# MCU.net
KiCad netlist of a schematic drawn in Altium Designer
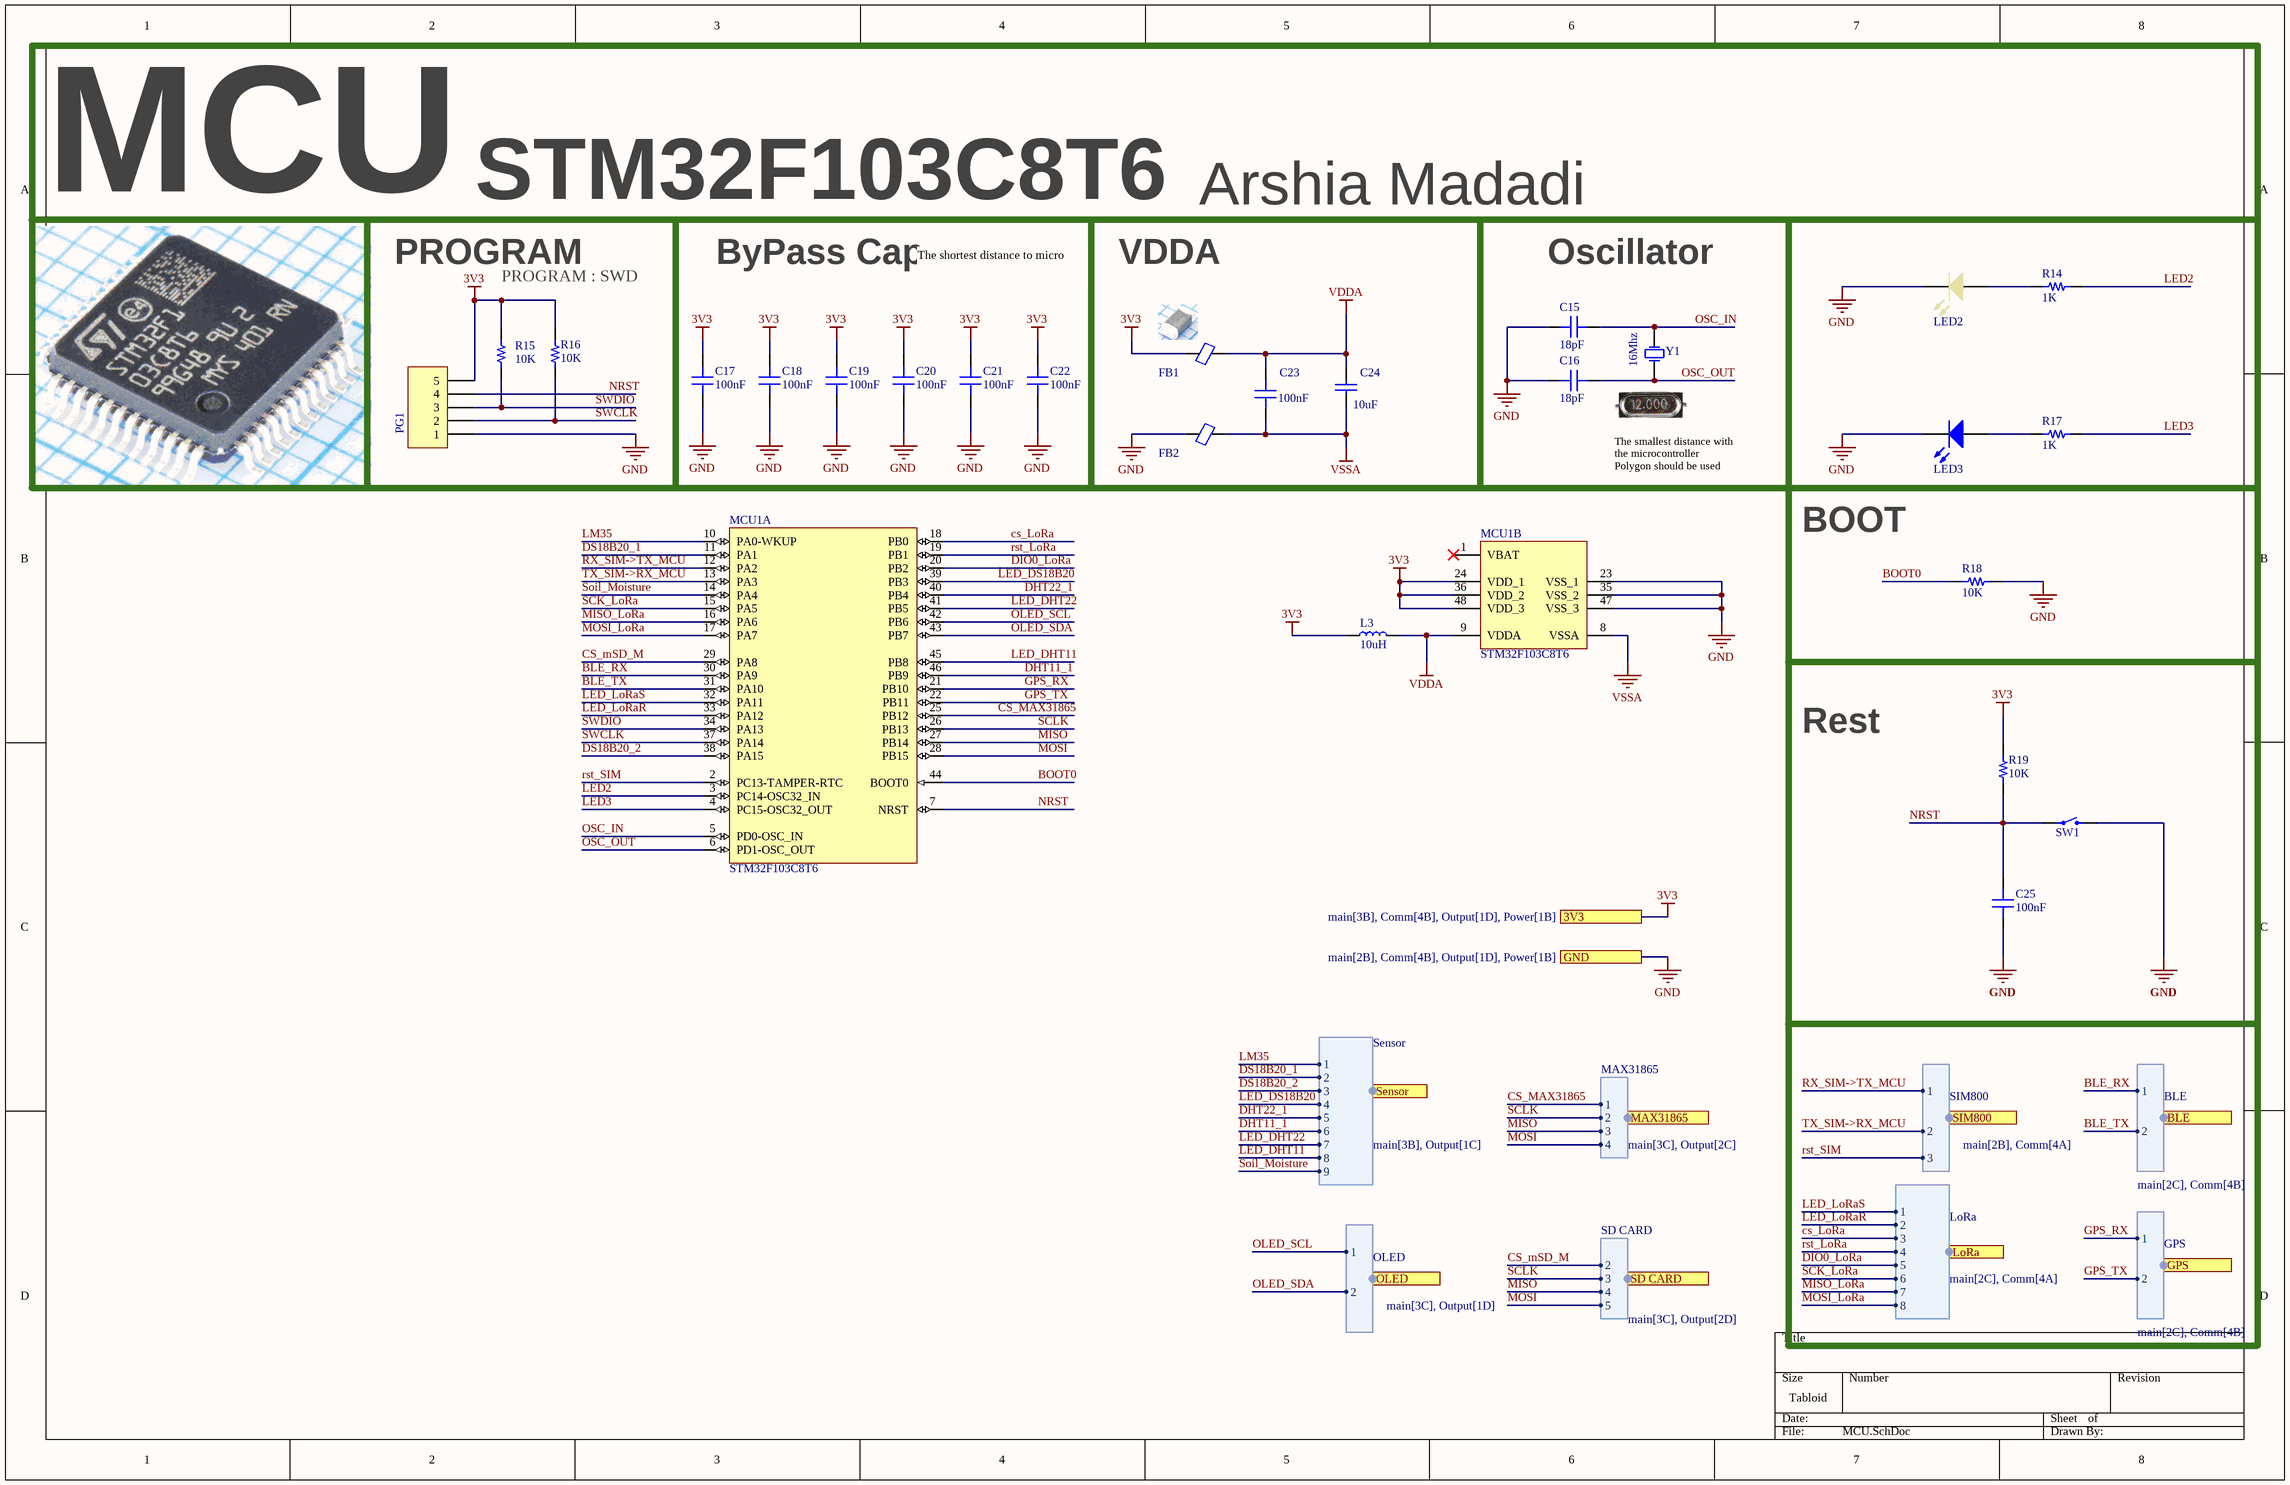
[diagram p0: MCU.SchDoc]

(export (version "E")
  (design (tool "Eeschema 10.0.6"))
  (components
    (comp (ref "C15")
      (value "18pF")
      (footprint "CAP 0603_1608")
      (description "SMT Capacitor")
      (libsource (lib "Capacitor") (part "Cap 0603"))
    )
    (comp (ref "C16")
      (value "18pF")
      (footprint "CAP 0603_1608")
      (description "SMT Capacitor")
      (libsource (lib "Capacitor") (part "Cap 0603"))
    )
    (comp (ref "C17")
      (value "100nF")
      (footprint "CAP 0603_1608")
      (description "SMT Capacitor")
      (libsource (lib "Capacitor") (part "Cap 0603"))
    )
    (comp (ref "C18")
      (value "100nF")
      (footprint "CAP 0603_1608")
      (description "SMT Capacitor")
      (libsource (lib "Capacitor") (part "Cap 0603"))
    )
    (comp (ref "C19")
      (value "100nF")
      (footprint "CAP 0603_1608")
      (description "SMT Capacitor")
      (libsource (lib "Capacitor") (part "Cap 0603"))
    )
    (comp (ref "C20")
      (value "100nF")
      (footprint "CAP 0603_1608")
      (description "SMT Capacitor")
      (libsource (lib "Capacitor") (part "Cap 0603"))
    )
    (comp (ref "C21")
      (value "100nF")
      (footprint "CAP 0603_1608")
      (description "SMT Capacitor")
      (libsource (lib "Capacitor") (part "Cap 0603"))
    )
    (comp (ref "C22")
      (value "100nF")
      (footprint "CAP 0603_1608")
      (description "SMT Capacitor")
      (libsource (lib "Capacitor") (part "Cap 0603"))
    )
    (comp (ref "C23")
      (value "100nF")
      (footprint "CAP 0603_1608")
      (description "SMT Capacitor")
      (libsource (lib "Capacitor") (part "Cap 0603"))
    )
    (comp (ref "C24")
      (value "10uF")
      (footprint "MY_CAP_SMD_0603")
      (description "1.6 mm × 0.8 mm")
      (libsource (lib "AMINLIB") (part "CAP SMD_0603"))
    )
    (comp (ref "C25")
      (value "100nF")
      (footprint "CAP 0603_1608")
      (description "SMT Capacitor")
      (libsource (lib "Capacitor") (part "Cap 0603"))
    )
    (comp (ref "FB1")
      (value "Ferrite Bead SMD")
      (footprint "FB1206")
      (fields (field (name "DESIGNER") "Ali Hafizi"))
      (libsource (lib "Altium") (part "Ferrite Bead SMD Package"))
    )
    (comp (ref "FB2")
      (value "Ferrite Bead SMD")
      (footprint "FB1206")
      (fields (field (name "DESIGNER") "Ali Hafizi"))
      (libsource (lib "Altium") (part "Ferrite Bead SMD Package"))
    )
    (comp (ref "L3")
      (value "10uH")
      (footprint "IND 1206_3216")
      (description "SMT Inductor")
      (libsource (lib "Inductor") (part "Ind 1206"))
    )
    (comp (ref "LED2")
      (value "LED SMD 0805 WHITE")
      (footprint "LED_0805_WHITE")
      (libsource (lib "Led") (part "LED SMD 0805 WHITE"))
    )
    (comp (ref "LED3")
      (value "LED SMD 0805 BLUE")
      (footprint "LED_0805_RED")
      (libsource (lib "Led") (part "LED SMD 0805 BLUE"))
    )
    (comp (ref "MCU1")
      (value "STM32F103C8T6")
      (footprint "QFP50P900X900X160-48N")
      (libsource (lib "STMicroelectronics STM32 F1") (part "STM32F103C8T6"))
    )
    (comp (ref "PG1")
      (value "Header 5")
      (footprint "My_1X05")
      (description "Header, 5-Pin")
      (fields (field (name "PUBLISHER") "Altium Limited"))
      (libsource (lib "AMINLIB") (part "Header 5"))
    )
    (comp (ref "R14")
      (value "1K")
      (footprint "RES 0603_1608")
      (description "SMT Resistor")
      (libsource (lib "Resistor") (part "Res 0603"))
    )
    (comp (ref "R15")
      (value "10K")
      (footprint "RES 0603_1608")
      (description "SMT Resistor")
      (libsource (lib "Resistor") (part "Res 0603"))
    )
    (comp (ref "R16")
      (value "10K")
      (footprint "RES 0603_1608")
      (description "SMT Resistor")
      (libsource (lib "Resistor") (part "Res 0603"))
    )
    (comp (ref "R17")
      (value "1K")
      (footprint "RES 0603_1608")
      (description "SMT Resistor")
      (libsource (lib "Resistor") (part "Res 0603"))
    )
    (comp (ref "R18")
      (value "10K")
      (footprint "RES 0603_1608")
      (description "SMT Resistor")
      (libsource (lib "Resistor") (part "Res 0603"))
    )
    (comp (ref "R19")
      (value "10K")
      (footprint "RES 0603_1608")
      (description "SMT Resistor")
      (libsource (lib "Resistor") (part "Res 0603"))
    )
    (comp (ref "SW1")
      (value "Tactile 2PIN 6X3.5mm H4.57mm (SMD)")
      (footprint "SWPBS_SPST_6X3X5")
      (description "Tactile Switch SPST-NO Top Actuated Surface Mount")
      (fields (field (name "PARTNUMBER") "FSMSMTR-ND"))
      (libsource (lib "Switch") (part "Tactile 2PIN 6X3.5mm H4.57mm (SMD)"))
    )
    (comp (ref "Y1")
      (value "16Mhz")
      (footprint "Crystal")
      (description "Crystal Oscillator")
      (fields (field (name "PUBLISHER") "Altium Limited"))
      (libsource (lib "Sajad_Altium_Library") (part "XTAL"))
    )
  )
  (nets
    (net (code "10") (name "/BLE_RX") (class "Default")
      (node (ref "MCU1") (pin "30") (pinfunction "PA9_30") (pintype "bidirectional"))
    )
    (net (code "11") (name "/BLE_TX") (class "Default")
      (node (ref "MCU1") (pin "31") (pinfunction "PA10_31") (pintype "bidirectional"))
    )
    (net (code "12") (name "/BOOT0") (class "Default")
      (node (ref "MCU1") (pin "44") (pinfunction "BOOT0_44") (pintype "input"))
      (node (ref "R18") (pin "2") (pinfunction "2_2") (pintype "passive"))
    )
    (net (code "13") (name "/CS_MAX31865") (class "Default")
      (node (ref "MCU1") (pin "25") (pinfunction "PB12_25") (pintype "bidirectional"))
    )
    (net (code "14") (name "/CS_mSD_M") (class "Default")
      (node (ref "MCU1") (pin "29") (pinfunction "PA8_29") (pintype "bidirectional"))
    )
    (net (code "15") (name "/DHT11_1") (class "Default")
      (node (ref "MCU1") (pin "46") (pinfunction "PB9_46") (pintype "bidirectional"))
    )
    (net (code "16") (name "/DHT22_1") (class "Default")
      (node (ref "MCU1") (pin "40") (pinfunction "PB4_40") (pintype "bidirectional"))
    )
    (net (code "17") (name "/DIO0_LoRa") (class "Default")
      (node (ref "MCU1") (pin "20") (pinfunction "PB2_20") (pintype "bidirectional"))
    )
    (net (code "18") (name "/DS18B20_1") (class "Default")
      (node (ref "MCU1") (pin "11") (pinfunction "PA1_11") (pintype "bidirectional"))
    )
    (net (code "19") (name "/DS18B20_2") (class "Default")
      (node (ref "MCU1") (pin "38") (pinfunction "PA15_38") (pintype "bidirectional"))
    )
    (net (code "20") (name "/GPS_RX") (class "Default")
      (node (ref "MCU1") (pin "21") (pinfunction "PB10_21") (pintype "bidirectional"))
    )
    (net (code "21") (name "/GPS_TX") (class "Default")
      (node (ref "MCU1") (pin "22") (pinfunction "PB11_22") (pintype "bidirectional"))
    )
    (net (code "22") (name "/LED2") (class "Default")
      (node (ref "MCU1") (pin "3") (pinfunction "PC14-OSC32_IN_3") (pintype "bidirectional"))
      (node (ref "R14") (pin "1") (pinfunction "1_1") (pintype "passive"))
    )
    (net (code "23") (name "/LED3") (class "Default")
      (node (ref "MCU1") (pin "4") (pinfunction "PC15-OSC32_OUT_4") (pintype "bidirectional"))
      (node (ref "R17") (pin "1") (pinfunction "1_1") (pintype "passive"))
    )
    (net (code "24") (name "/LED_DHT11") (class "Default")
      (node (ref "MCU1") (pin "45") (pinfunction "PB8_45") (pintype "bidirectional"))
    )
    (net (code "25") (name "/LED_DHT22") (class "Default")
      (node (ref "MCU1") (pin "41") (pinfunction "PB5_41") (pintype "bidirectional"))
    )
    (net (code "26") (name "/LED_DS18B20") (class "Default")
      (node (ref "MCU1") (pin "39") (pinfunction "PB3_39") (pintype "bidirectional"))
    )
    (net (code "27") (name "/LED_LoRaR") (class "Default")
      (node (ref "MCU1") (pin "33") (pinfunction "PA12_33") (pintype "bidirectional"))
    )
    (net (code "28") (name "/LED_LoRaS") (class "Default")
      (node (ref "MCU1") (pin "32") (pinfunction "PA11_32") (pintype "bidirectional"))
    )
    (net (code "29") (name "/LM35") (class "Default")
      (node (ref "MCU1") (pin "10") (pinfunction "PA0-WKUP_10") (pintype "bidirectional"))
    )
    (net (code "30") (name "/MISO") (class "Default")
      (node (ref "MCU1") (pin "27") (pinfunction "PB14_27") (pintype "bidirectional"))
    )
    (net (code "31") (name "/MISO_LoRa") (class "Default")
      (node (ref "MCU1") (pin "16") (pinfunction "PA6_16") (pintype "bidirectional"))
    )
    (net (code "32") (name "/MOSI") (class "Default")
      (node (ref "MCU1") (pin "28") (pinfunction "PB15_28") (pintype "bidirectional"))
    )
    (net (code "33") (name "/MOSI_LoRa") (class "Default")
      (node (ref "MCU1") (pin "17") (pinfunction "PA7_17") (pintype "bidirectional"))
    )
    (net (code "34") (name "/NRST") (class "Default")
      (node (ref "C25") (pin "2") (pinfunction "2_2") (pintype "passive"))
      (node (ref "MCU1") (pin "7") (pinfunction "NRST_7") (pintype "bidirectional"))
      (node (ref "PG1") (pin "4") (pinfunction "4_4") (pintype "passive"))
      (node (ref "R19") (pin "2") (pinfunction "2_2") (pintype "passive"))
      (node (ref "SW1") (pin "1") (pinfunction "1_1") (pintype "passive"))
    )
    (net (code "35") (name "/OLED_SCL") (class "Default")
      (node (ref "MCU1") (pin "42") (pinfunction "PB6_42") (pintype "bidirectional"))
    )
    (net (code "36") (name "/OLED_SDA") (class "Default")
      (node (ref "MCU1") (pin "43") (pinfunction "PB7_43") (pintype "bidirectional"))
    )
    (net (code "37") (name "/OSC_IN") (class "Default")
      (node (ref "C15") (pin "1") (pinfunction "1_1") (pintype "passive"))
      (node (ref "MCU1") (pin "5") (pinfunction "PD0-OSC_IN_5") (pintype "bidirectional"))
      (node (ref "Y1") (pin "2") (pinfunction "OSC2_2") (pintype "passive"))
    )
    (net (code "38") (name "/OSC_OUT") (class "Default")
      (node (ref "C16") (pin "1") (pinfunction "1_1") (pintype "passive"))
      (node (ref "MCU1") (pin "6") (pinfunction "PD1-OSC_OUT_6") (pintype "bidirectional"))
      (node (ref "Y1") (pin "1") (pinfunction "OSC1_1") (pintype "passive"))
    )
    (net (code "39") (name "/RX_SIM->TX_MCU") (class "Default")
      (node (ref "MCU1") (pin "12") (pinfunction "PA2_12") (pintype "bidirectional"))
    )
    (net (code "40") (name "/SCK_LoRa") (class "Default")
      (node (ref "MCU1") (pin "15") (pinfunction "PA5_15") (pintype "bidirectional"))
    )
    (net (code "41") (name "/SCLK") (class "Default")
      (node (ref "MCU1") (pin "26") (pinfunction "PB13_26") (pintype "bidirectional"))
    )
    (net (code "42") (name "/SWCLK") (class "Default")
      (node (ref "MCU1") (pin "37") (pinfunction "PA14_37") (pintype "bidirectional"))
      (node (ref "PG1") (pin "2") (pinfunction "2_2") (pintype "passive"))
      (node (ref "R16") (pin "2") (pinfunction "2_2") (pintype "passive"))
    )
    (net (code "43") (name "/SWDIO") (class "Default")
      (node (ref "MCU1") (pin "34") (pinfunction "PA13_34") (pintype "bidirectional"))
      (node (ref "PG1") (pin "3") (pinfunction "3_3") (pintype "passive"))
      (node (ref "R15") (pin "2") (pinfunction "2_2") (pintype "passive"))
    )
    (net (code "44") (name "/Soil_Moisture") (class "Default")
      (node (ref "MCU1") (pin "14") (pinfunction "PA4_14") (pintype "bidirectional"))
    )
    (net (code "45") (name "/TX_SIM->RX_MCU") (class "Default")
      (node (ref "MCU1") (pin "13") (pinfunction "PA3_13") (pintype "bidirectional"))
    )
    (net (code "46") (name "/cs_LoRa") (class "Default")
      (node (ref "MCU1") (pin "18") (pinfunction "PB0_18") (pintype "bidirectional"))
    )
    (net (code "47") (name "/rst_LoRa") (class "Default")
      (node (ref "MCU1") (pin "19") (pinfunction "PB1_19") (pintype "bidirectional"))
    )
    (net (code "48") (name "/rst_SIM") (class "Default")
      (node (ref "MCU1") (pin "2") (pinfunction "PC13-TAMPER-RTC_2") (pintype "bidirectional"))
    )
    (net (code "57") (name "3V3") (class "Default")
      (node (ref "C17") (pin "2") (pinfunction "2_2") (pintype "passive"))
      (node (ref "C18") (pin "2") (pinfunction "2_2") (pintype "passive"))
      (node (ref "C19") (pin "2") (pinfunction "2_2") (pintype "passive"))
      (node (ref "C20") (pin "2") (pinfunction "2_2") (pintype "passive"))
      (node (ref "C21") (pin "2") (pinfunction "2_2") (pintype "passive"))
      (node (ref "C22") (pin "2") (pinfunction "2_2") (pintype "passive"))
      (node (ref "FB1") (pin "1") (pinfunction "1_1") (pintype "passive"))
      (node (ref "L3") (pin "1") (pinfunction "1_1") (pintype "passive"))
      (node (ref "MCU1") (pin "24") (pinfunction "VDD_1_24") (pintype "power_in"))
      (node (ref "MCU1") (pin "36") (pinfunction "VDD_2_36") (pintype "power_in"))
      (node (ref "MCU1") (pin "48") (pinfunction "VDD_3_48") (pintype "power_in"))
      (node (ref "PG1") (pin "5") (pinfunction "5_5") (pintype "passive"))
      (node (ref "R15") (pin "1") (pinfunction "1_1") (pintype "passive"))
      (node (ref "R16") (pin "1") (pinfunction "1_1") (pintype "passive"))
      (node (ref "R19") (pin "1") (pinfunction "1_1") (pintype "passive"))
    )
    (net (code "58") (name "GND") (class "Default")
      (node (ref "C15") (pin "2") (pinfunction "2_2") (pintype "passive"))
      (node (ref "C16") (pin "2") (pinfunction "2_2") (pintype "passive"))
      (node (ref "C17") (pin "1") (pinfunction "1_1") (pintype "passive"))
      (node (ref "C18") (pin "1") (pinfunction "1_1") (pintype "passive"))
      (node (ref "C19") (pin "1") (pinfunction "1_1") (pintype "passive"))
      (node (ref "C20") (pin "1") (pinfunction "1_1") (pintype "passive"))
      (node (ref "C21") (pin "1") (pinfunction "1_1") (pintype "passive"))
      (node (ref "C22") (pin "1") (pinfunction "1_1") (pintype "passive"))
      (node (ref "C25") (pin "1") (pinfunction "1_1") (pintype "passive"))
      (node (ref "FB2") (pin "1") (pinfunction "1_1") (pintype "passive"))
      (node (ref "LED2") (pin "2") (pinfunction "K_2") (pintype "passive"))
      (node (ref "LED3") (pin "2") (pinfunction "K_2") (pintype "passive"))
      (node (ref "MCU1") (pin "23") (pinfunction "VSS_1_23") (pintype "power_in"))
      (node (ref "MCU1") (pin "35") (pinfunction "VSS_2_35") (pintype "power_in"))
      (node (ref "MCU1") (pin "47") (pinfunction "VSS_3_47") (pintype "power_in"))
      (node (ref "PG1") (pin "1") (pinfunction "1_1") (pintype "passive"))
      (node (ref "R18") (pin "1") (pinfunction "1_1") (pintype "passive"))
      (node (ref "SW1") (pin "2") (pinfunction "2_2") (pintype "passive"))
    )
    (net (code "59") (name "Net-(LED2-A)") (class "Default")
      (node (ref "LED2") (pin "1") (pinfunction "A_1") (pintype "passive"))
      (node (ref "R14") (pin "2") (pinfunction "2_2") (pintype "passive"))
    )
    (net (code "60") (name "Net-(LED3-A)") (class "Default")
      (node (ref "LED3") (pin "1") (pinfunction "A_1") (pintype "passive"))
      (node (ref "R17") (pin "2") (pinfunction "2_2") (pintype "passive"))
    )
    (net (code "61") (name "VDDA") (class "Default")
      (node (ref "C23") (pin "2") (pinfunction "2_2") (pintype "passive"))
      (node (ref "C24") (pin "1") (pinfunction "1_1") (pintype "passive"))
      (node (ref "FB1") (pin "2") (pinfunction "2_2") (pintype "passive"))
      (node (ref "L3") (pin "2") (pinfunction "2_2") (pintype "passive"))
      (node (ref "MCU1") (pin "9") (pinfunction "VDDA_9") (pintype "power_in"))
    )
    (net (code "62") (name "VSSA") (class "Default")
      (node (ref "C23") (pin "1") (pinfunction "1_1") (pintype "passive"))
      (node (ref "C24") (pin "2") (pinfunction "2_2") (pintype "passive"))
      (node (ref "FB2") (pin "2") (pinfunction "2_2") (pintype "passive"))
      (node (ref "MCU1") (pin "8") (pinfunction "VSSA_8") (pintype "power_in"))
    )
    (net (code "63") (name "unconnected-(MCU1B-VBAT-Pad1)") (class "Default")
      (node (ref "MCU1") (pin "1") (pinfunction "VBAT_1") (pintype "power_in+no_connect"))
    )
  )
)
